# fc.net
KiCad netlist of a schematic drawn in EAGLE
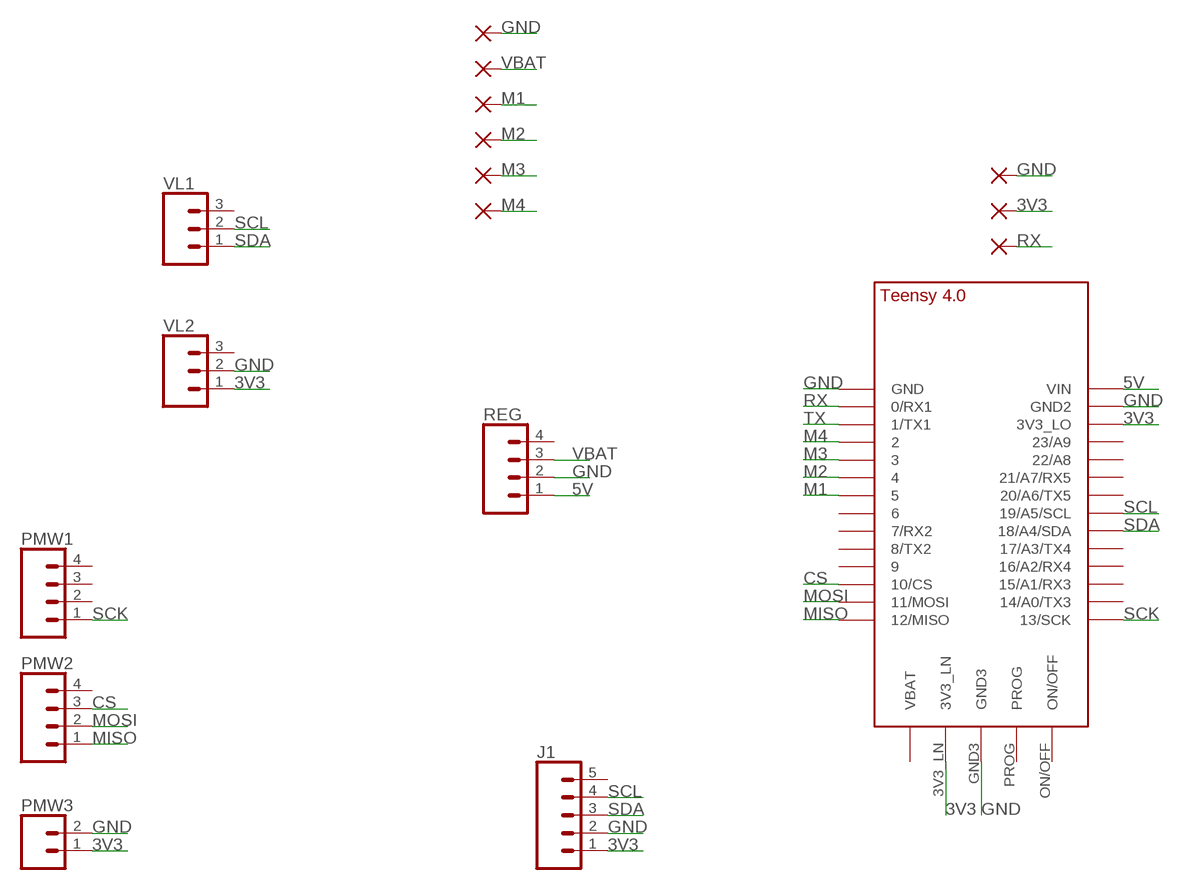
[diagram p0: schematic, sheet 1]

(export (version "E")
  (design (tool "Eeschema 10.0.6"))
  (components
    (comp (ref "3V")
      (value "SMD2")
      (footprint "eagle-import:SMD1,27-2,54")
      (libsource (lib "eagle-import") (part "SMD2"))
    )
    (comp (ref "GD")
      (value "SMD2")
      (footprint "eagle-import:SMD1,27-2,54")
      (libsource (lib "eagle-import") (part "SMD2"))
    )
    (comp (ref "GND")
      (value "SMD2")
      (footprint "eagle-import:SMD1,27-2,54")
      (libsource (lib "eagle-import") (part "SMD2"))
    )
    (comp (ref "J1")
      (value "CONN_05NO_SILK")
      (footprint "eagle-import:1X05_NO_SILK")
      (libsource (lib "eagle-import") (part "CONN_05NO_SILK"))
    )
    (comp (ref "M1")
      (value "SMD2")
      (footprint "eagle-import:SMD1,27-2,54")
      (libsource (lib "eagle-import") (part "SMD2"))
    )
    (comp (ref "M2")
      (value "SMD2")
      (footprint "eagle-import:SMD1,27-2,54")
      (libsource (lib "eagle-import") (part "SMD2"))
    )
    (comp (ref "M3")
      (value "SMD2")
      (footprint "eagle-import:SMD1,27-2,54")
      (libsource (lib "eagle-import") (part "SMD2"))
    )
    (comp (ref "M4")
      (value "SMD2")
      (footprint "eagle-import:SMD1,27-2,54")
      (libsource (lib "eagle-import") (part "SMD2"))
    )
    (comp (ref "PMW1")
      (value "CONN_041X04_NO_SILK")
      (footprint "eagle-import:1X04_NO_SILK")
      (libsource (lib "eagle-import") (part "CONN_041X04_NO_SILK"))
    )
    (comp (ref "PMW2")
      (value "CONN_041X04_NO_SILK")
      (footprint "eagle-import:1X04_NO_SILK")
      (libsource (lib "eagle-import") (part "CONN_041X04_NO_SILK"))
    )
    (comp (ref "PMW3")
      (value "CONN_021X02_NO_SILK")
      (footprint "eagle-import:1X02_NO_SILK")
      (libsource (lib "eagle-import") (part "CONN_021X02_NO_SILK"))
    )
    (comp (ref "REG")
      (value "CONN_041X04_NO_SILK")
      (footprint "eagle-import:1X04_NO_SILK")
      (libsource (lib "eagle-import") (part "CONN_041X04_NO_SILK"))
    )
    (comp (ref "RX")
      (value "SMD2")
      (footprint "eagle-import:SMD1,27-2,54")
      (libsource (lib "eagle-import") (part "SMD2"))
    )
    (comp (ref "U$1")
      (value "TEENSY_4.0")
      (footprint "eagle-import:TEENSY_4.0")
      (libsource (lib "eagle-import") (part "TEENSY_4.0"))
    )
    (comp (ref "VBAT")
      (value "SMD2")
      (footprint "eagle-import:SMD1,27-2,54")
      (libsource (lib "eagle-import") (part "SMD2"))
    )
    (comp (ref "VL1")
      (value "CONN_031X03_NO_SILK")
      (footprint "eagle-import:1X03_NO_SILK")
      (libsource (lib "eagle-import") (part "CONN_031X03_NO_SILK"))
    )
    (comp (ref "VL2")
      (value "CONN_031X03_NO_SILK")
      (footprint "eagle-import:1X03_NO_SILK")
      (libsource (lib "eagle-import") (part "CONN_031X03_NO_SILK"))
    )
  )
  (nets
    (net (code "1") (name "/3V3") (class "Default")
      (node (ref "3V") (pin "1") (pinfunction "P_1") (pintype "passive"))
      (node (ref "J1") (pin "1") (pinfunction "1_1") (pintype "passive"))
      (node (ref "PMW3") (pin "1") (pinfunction "1_1") (pintype "passive"))
      (node (ref "U$1") (pin "3V3_LN") (pinfunction "3V3_LN_3V3_LN") (pintype "bidirectional"))
      (node (ref "U$1") (pin "3V3_LO") (pinfunction "3V3_LO_3V3_LO") (pintype "bidirectional"))
      (node (ref "VL2") (pin "1") (pinfunction "1_1") (pintype "passive"))
    )
    (net (code "2") (name "/5V") (class "Default")
      (node (ref "REG") (pin "1") (pinfunction "1_1") (pintype "passive"))
      (node (ref "U$1") (pin "VIN") (pinfunction "VIN_VIN") (pintype "bidirectional"))
    )
    (net (code "3") (name "/CS") (class "Default")
      (node (ref "PMW2") (pin "3") (pinfunction "3_3") (pintype "passive"))
      (node (ref "U$1") (pin "10/CS") (pinfunction "10/CS_10/CS") (pintype "bidirectional"))
    )
    (net (code "4") (name "/GND") (class "Default")
      (node (ref "GD") (pin "1") (pinfunction "P_1") (pintype "passive"))
      (node (ref "GND") (pin "1") (pinfunction "P_1") (pintype "passive"))
      (node (ref "J1") (pin "2") (pinfunction "2_2") (pintype "passive"))
      (node (ref "PMW3") (pin "2") (pinfunction "2_2") (pintype "passive"))
      (node (ref "REG") (pin "2") (pinfunction "2_2") (pintype "passive"))
      (node (ref "U$1") (pin "GND") (pinfunction "GND_GND") (pintype "bidirectional"))
      (node (ref "U$1") (pin "GND2") (pinfunction "GND2_GND2") (pintype "bidirectional"))
      (node (ref "U$1") (pin "GND3") (pinfunction "GND3_GND3") (pintype "bidirectional"))
      (node (ref "VL2") (pin "2") (pinfunction "2_2") (pintype "passive"))
    )
    (net (code "5") (name "/M1") (class "Default")
      (node (ref "M4") (pin "1") (pinfunction "P_1") (pintype "passive"))
      (node (ref "U$1") (pin "5") (pinfunction "5_5") (pintype "bidirectional"))
    )
    (net (code "6") (name "/M2") (class "Default")
      (node (ref "M3") (pin "1") (pinfunction "P_1") (pintype "passive"))
      (node (ref "U$1") (pin "4/CANRX") (pinfunction "4_4/CANRX") (pintype "bidirectional"))
    )
    (net (code "7") (name "/M3") (class "Default")
      (node (ref "M2") (pin "1") (pinfunction "P_1") (pintype "passive"))
      (node (ref "U$1") (pin "3/CANTX") (pinfunction "3_3/CANTX") (pintype "bidirectional"))
    )
    (net (code "8") (name "/M4") (class "Default")
      (node (ref "M1") (pin "1") (pinfunction "P_1") (pintype "passive"))
      (node (ref "U$1") (pin "2") (pinfunction "2_2") (pintype "bidirectional"))
    )
    (net (code "9") (name "/MISO") (class "Default")
      (node (ref "PMW2") (pin "1") (pinfunction "1_1") (pintype "passive"))
      (node (ref "U$1") (pin "12/MISO") (pinfunction "12/MISO_12/MISO") (pintype "bidirectional"))
    )
    (net (code "10") (name "/MOSI") (class "Default")
      (node (ref "PMW2") (pin "2") (pinfunction "2_2") (pintype "passive"))
      (node (ref "U$1") (pin "11/MOSI") (pinfunction "11/MOSI_11/MOSI") (pintype "bidirectional"))
    )
    (net (code "11") (name "/RX") (class "Default")
      (node (ref "RX") (pin "1") (pinfunction "P_1") (pintype "passive"))
      (node (ref "U$1") (pin "0/RX") (pinfunction "0/RX1_0/RX") (pintype "bidirectional"))
    )
    (net (code "12") (name "/SCK") (class "Default")
      (node (ref "PMW1") (pin "1") (pinfunction "1_1") (pintype "passive"))
      (node (ref "U$1") (pin "13/SCK") (pinfunction "13/SCK_13/SCK") (pintype "bidirectional"))
    )
    (net (code "13") (name "/SCL") (class "Default")
      (node (ref "J1") (pin "4") (pinfunction "4_4") (pintype "passive"))
      (node (ref "U$1") (pin "19/A5/SCL") (pinfunction "19/A5/SCL_19/A5/SCL") (pintype "bidirectional"))
      (node (ref "VL1") (pin "2") (pinfunction "2_2") (pintype "passive"))
    )
    (net (code "14") (name "/SDA") (class "Default")
      (node (ref "J1") (pin "3") (pinfunction "3_3") (pintype "passive"))
      (node (ref "U$1") (pin "18/A4/SDA") (pinfunction "18/A4/SDA_18/A4/SDA") (pintype "bidirectional"))
      (node (ref "VL1") (pin "1") (pinfunction "1_1") (pintype "passive"))
    )
    (net (code "15") (name "/TX") (class "Default")
      (node (ref "U$1") (pin "1/TX") (pinfunction "1/TX1_1/TX") (pintype "bidirectional"))
    )
    (net (code "16") (name "/VBAT") (class "Default")
      (node (ref "REG") (pin "3") (pinfunction "3_3") (pintype "passive"))
      (node (ref "VBAT") (pin "1") (pinfunction "P_1") (pintype "passive"))
    )
    (net (code "17") (name "unconnected-(J1-Pad5)") (class "Default")
      (node (ref "J1") (pin "5") (pinfunction "5_5") (pintype "passive"))
    )
    (net (code "18") (name "unconnected-(PMW1-Pad2)") (class "Default")
      (node (ref "PMW1") (pin "2") (pinfunction "2_2") (pintype "passive"))
    )
    (net (code "19") (name "unconnected-(PMW1-Pad3)") (class "Default")
      (node (ref "PMW1") (pin "3") (pinfunction "3_3") (pintype "passive"))
    )
    (net (code "20") (name "unconnected-(PMW1-Pad4)") (class "Default")
      (node (ref "PMW1") (pin "4") (pinfunction "4_4") (pintype "passive"))
    )
    (net (code "21") (name "unconnected-(PMW2-Pad4)") (class "Default")
      (node (ref "PMW2") (pin "4") (pinfunction "4_4") (pintype "passive"))
    )
    (net (code "22") (name "unconnected-(REG-Pad4)") (class "Default")
      (node (ref "REG") (pin "4") (pinfunction "4_4") (pintype "passive"))
    )
    (net (code "23") (name "unconnected-(U$1-7{slash}RX2-Pad7)") (class "Default")
      (node (ref "U$1") (pin "7") (pinfunction "7/RX2_7") (pintype "bidirectional"))
    )
    (net (code "24") (name "unconnected-(U$1-8{slash}TX2-Pad8)") (class "Default")
      (node (ref "U$1") (pin "8") (pinfunction "8/TX2_8") (pintype "bidirectional"))
    )
    (net (code "25") (name "unconnected-(U$1-9-Pad9{slash}CS)") (class "Default")
      (node (ref "U$1") (pin "9/CS") (pinfunction "9_9/CS") (pintype "bidirectional"))
    )
    (net (code "26") (name "unconnected-(U$1-14{slash}A0{slash}TX3-Pad14{slash}A0)") (class "Default")
      (node (ref "U$1") (pin "14/A0") (pinfunction "14/A0/TX3_14/A0") (pintype "bidirectional"))
    )
    (net (code "27") (name "unconnected-(U$1-15{slash}A1{slash}RX3-Pad15{slash}A1)") (class "Default")
      (node (ref "U$1") (pin "15/A1") (pinfunction "15/A1/RX3_15/A1") (pintype "bidirectional"))
    )
    (net (code "28") (name "unconnected-(U$1-16{slash}A2{slash}RX4-Pad16{slash}A2)") (class "Default")
      (node (ref "U$1") (pin "16/A2") (pinfunction "16/A2/RX4_16/A2") (pintype "bidirectional"))
    )
    (net (code "29") (name "unconnected-(U$1-17{slash}A3{slash}TX4-Pad17{slash}A3)") (class "Default")
      (node (ref "U$1") (pin "17/A3") (pinfunction "17/A3/TX4_17/A3") (pintype "bidirectional"))
    )
    (net (code "30") (name "unconnected-(U$1-20{slash}A6{slash}TX5-Pad20{slash}A6)") (class "Default")
      (node (ref "U$1") (pin "20/A6") (pinfunction "20/A6/TX5_20/A6") (pintype "bidirectional"))
    )
    (net (code "31") (name "unconnected-(U$1-21{slash}A7{slash}RX5-Pad21{slash}A7)") (class "Default")
      (node (ref "U$1") (pin "21/A7") (pinfunction "21/A7/RX5_21/A7") (pintype "bidirectional"))
    )
    (net (code "32") (name "unconnected-(U$1-Pad6)") (class "Default")
      (node (ref "U$1") (pin "6") (pinfunction "6_6") (pintype "bidirectional"))
    )
    (net (code "33") (name "unconnected-(U$1-Pad22{slash}A8)") (class "Default")
      (node (ref "U$1") (pin "22/A8") (pinfunction "22/A8_22/A8") (pintype "bidirectional"))
    )
    (net (code "34") (name "unconnected-(U$1-Pad23{slash}A9)") (class "Default")
      (node (ref "U$1") (pin "23/A9") (pinfunction "23/A9_23/A9") (pintype "bidirectional"))
    )
    (net (code "35") (name "unconnected-(U$1-PadON{slash}OFF)") (class "Default")
      (node (ref "U$1") (pin "ON/OFF") (pinfunction "ON/OFF_ON/OFF") (pintype "bidirectional"))
    )
    (net (code "36") (name "unconnected-(U$1-PadPROG)") (class "Default")
      (node (ref "U$1") (pin "PROG") (pinfunction "PROG_PROG") (pintype "bidirectional"))
    )
    (net (code "37") (name "unconnected-(U$1-VBAT-PadVBAT\\)") (class "Default")
      (node (ref "U$1") (pin "VBAT\\") (pinfunction "VBAT_VBAT\\") (pintype "bidirectional"))
    )
    (net (code "38") (name "unconnected-(VL1-Pad3)") (class "Default")
      (node (ref "VL1") (pin "3") (pinfunction "3_3") (pintype "passive"))
    )
    (net (code "39") (name "unconnected-(VL2-Pad3)") (class "Default")
      (node (ref "VL2") (pin "3") (pinfunction "3_3") (pintype "passive"))
    )
  )
)
